# S7CAS-PLEIADES-CARTE-MERE_P06_FPGA2.net
KiCad netlist of a schematic drawn in Altium Designer
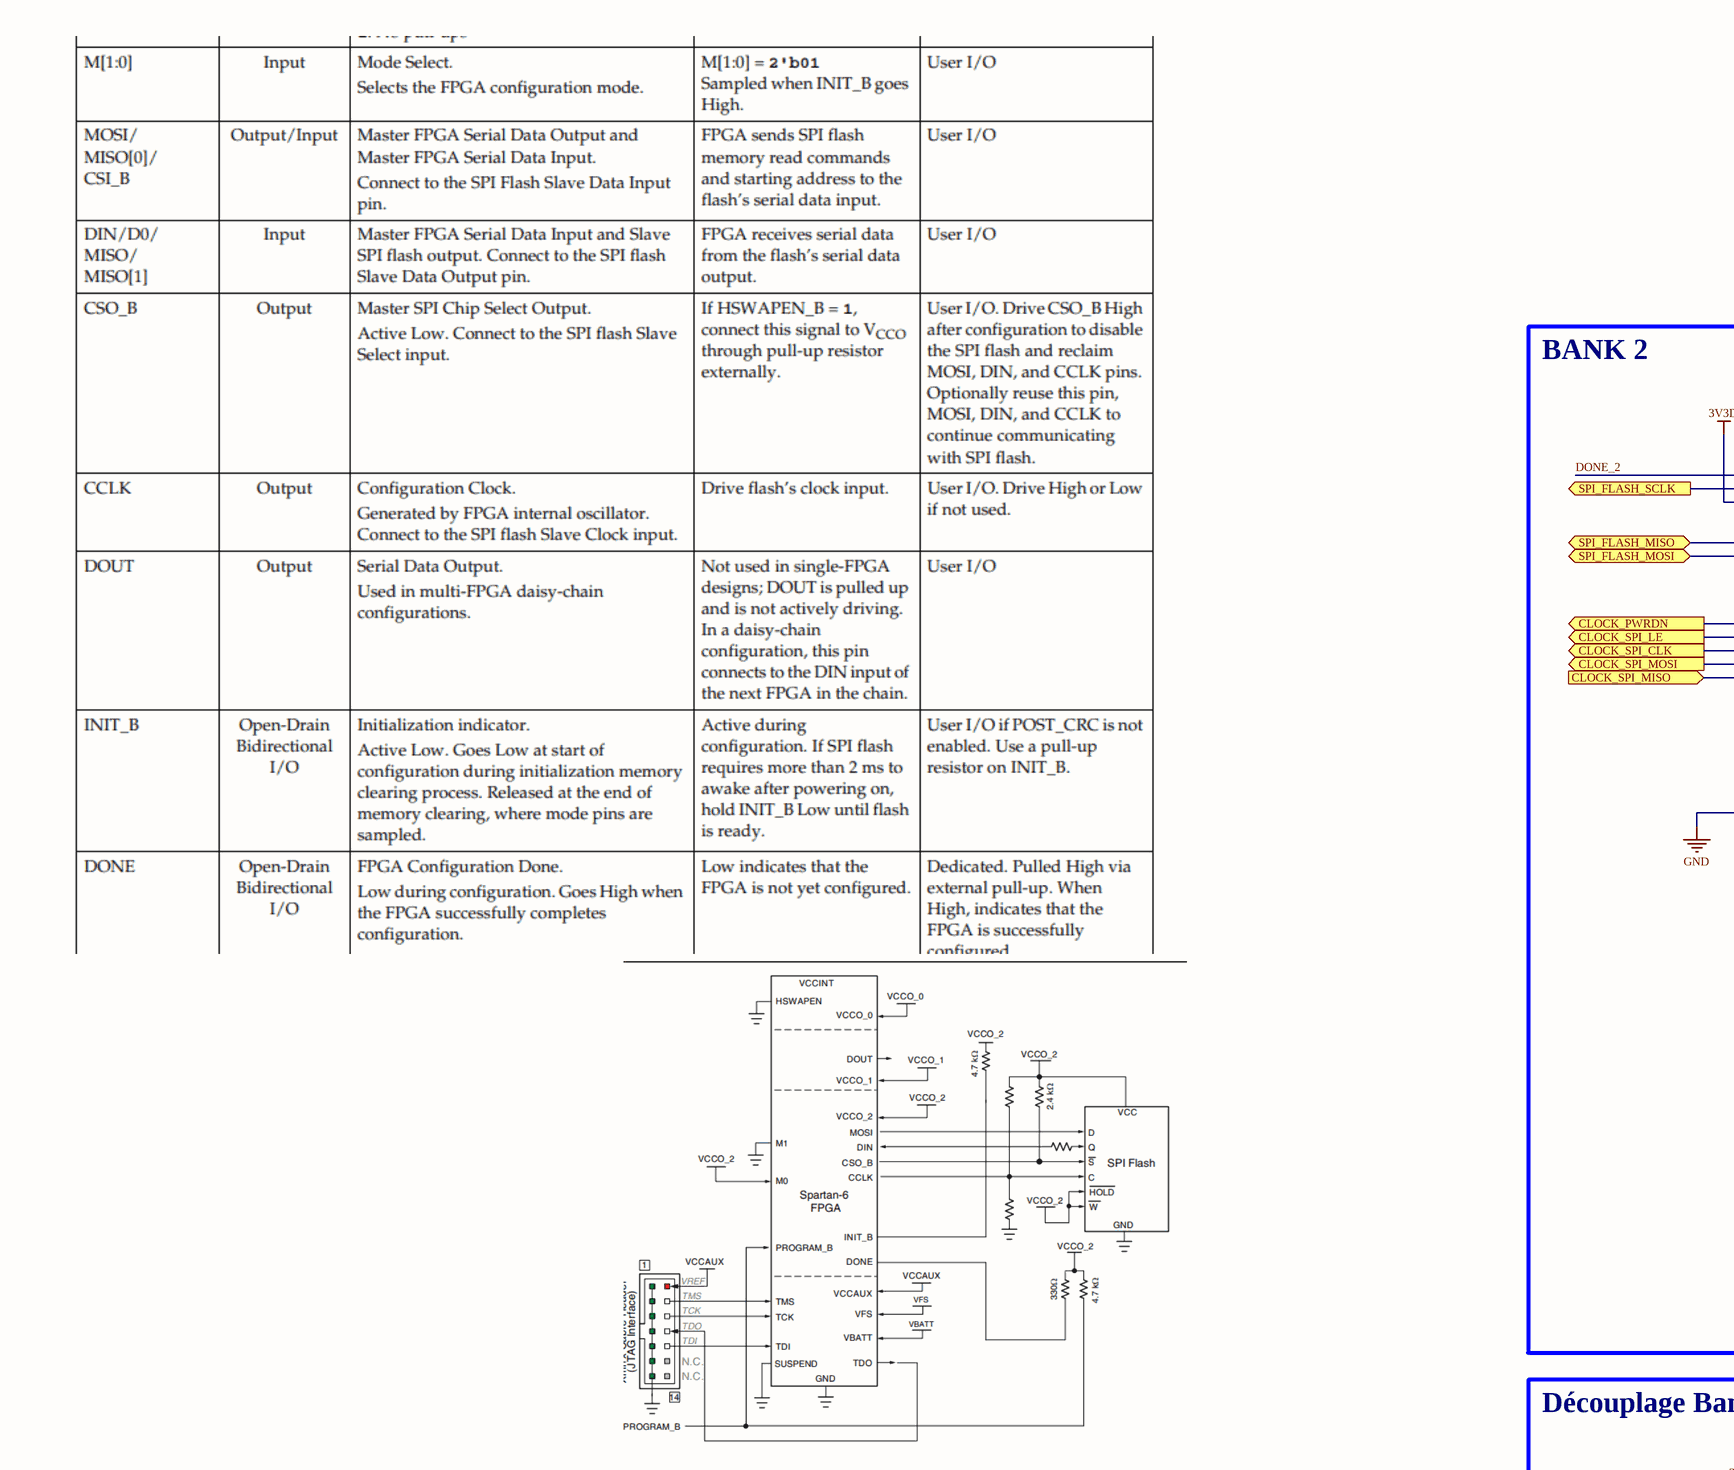
[diagram p0: S7CAS-PLEIADES-CARTE-MERE_P06_FPGA2.SCHDOC, top left]
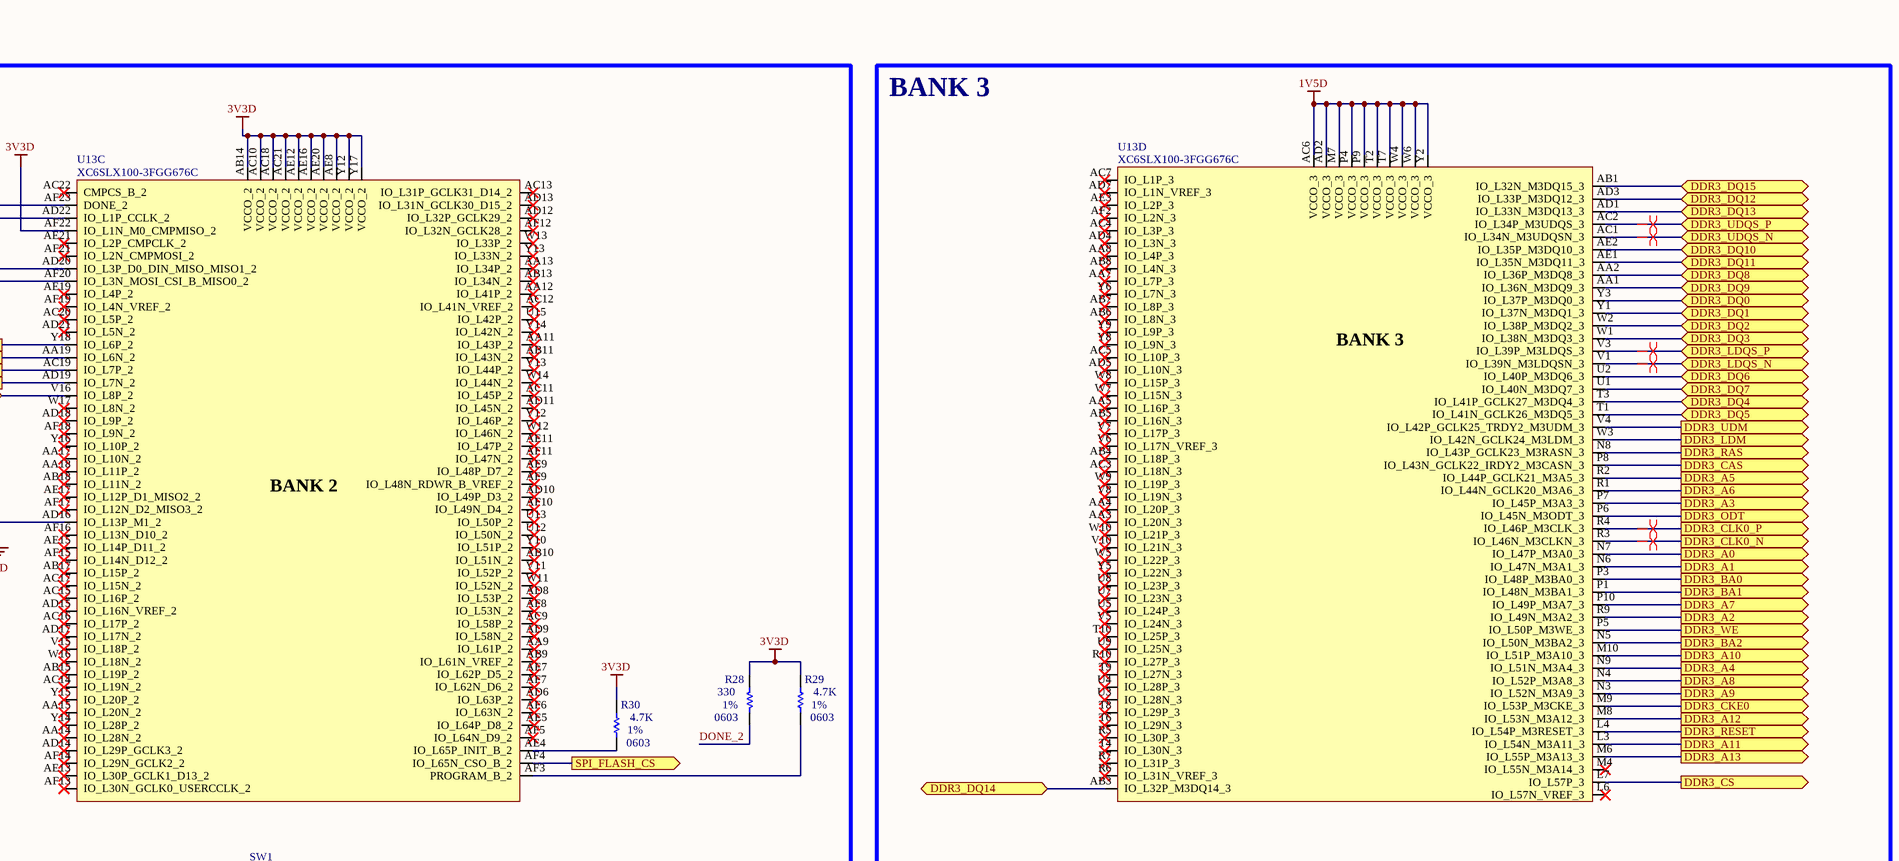
[diagram p1: S7CAS-PLEIADES-CARTE-MERE_P06_FPGA2.SCHDOC, top right]
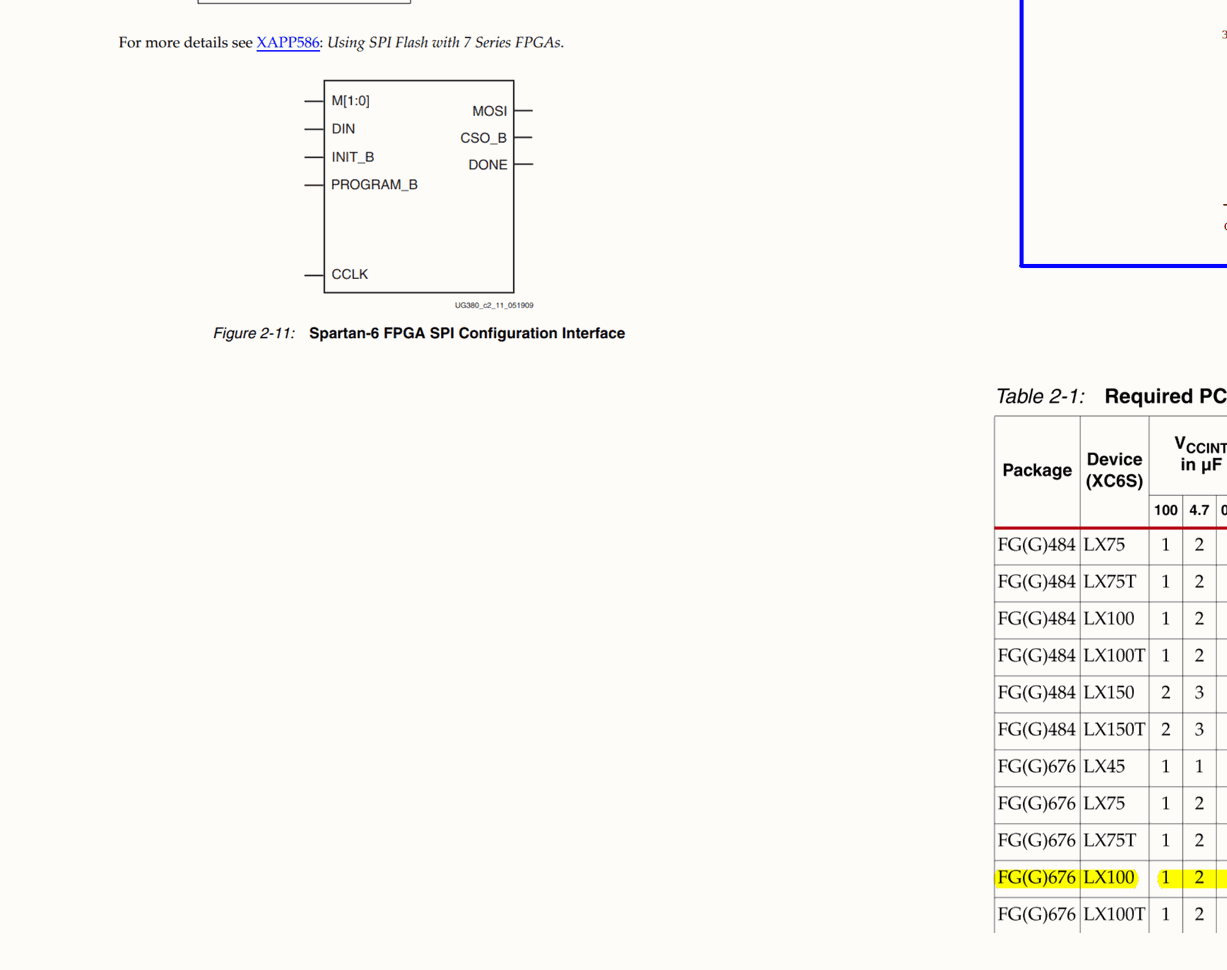
[diagram p2: S7CAS-PLEIADES-CARTE-MERE_P06_FPGA2.SCHDOC, bottom left]
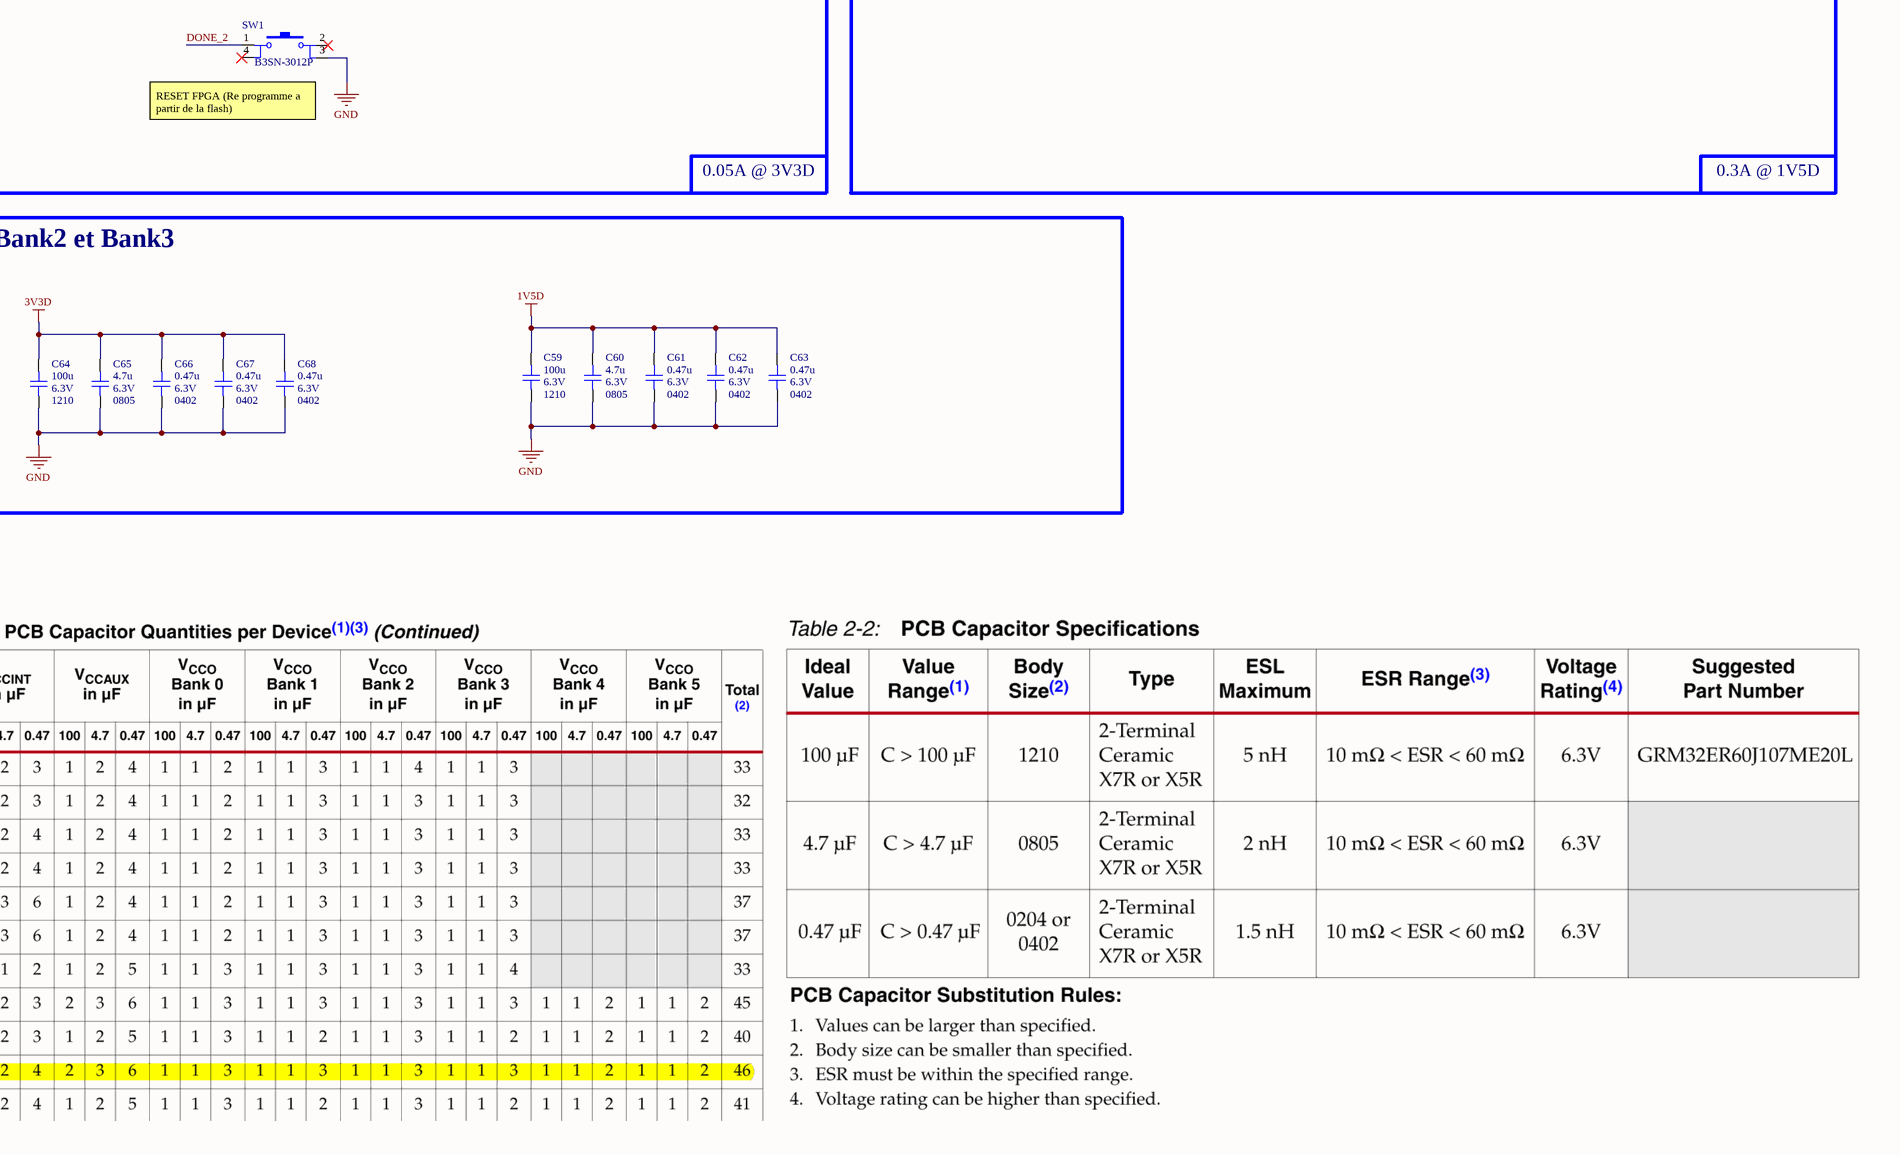
[diagram p3: S7CAS-PLEIADES-CARTE-MERE_P06_FPGA2.SCHDOC, bottom right]

(export (version "E")
  (design (tool "Eeschema 10.0.6"))
  (components
    (comp (ref "C59")
      (value "100u")
      (footprint "CAP_1210")
      (description "CAP - 1210")
      (fields
        (field (name "VOLTAGE") "6.3V")
        (field (name "PACKAGE") "1210")
        (field (name "CREATEDBY") "Jonathan Bouchard")
      )
      (libsource (lib "s7cas_lib2023") (part "CAP - 1210"))
    )
    (comp (ref "C60")
      (value "4.7u")
      (footprint "CAP_0805")
      (description "CAP - 0805")
      (fields
        (field (name "VOLTAGE") "6.3V")
        (field (name "PACKAGE") "0805")
        (field (name "CREATEDBY") "Jonathan Bouchard")
      )
      (libsource (lib "s7cas_lib2023") (part "CAP - 0805"))
    )
    (comp (ref "C61")
      (value "0.47u")
      (footprint "CAP_0402")
      (description "CAP - 0402")
      (fields
        (field (name "VOLTAGE") "6.3V")
        (field (name "PACKAGE") "0402")
        (field (name "CREATEDBY") "Jonathan Bouchard")
      )
      (libsource (lib "s7cas_lib2023") (part "CAP - 0402"))
    )
    (comp (ref "C62")
      (value "0.47u")
      (footprint "CAP_0402")
      (description "CAP - 0402")
      (fields
        (field (name "VOLTAGE") "6.3V")
        (field (name "PACKAGE") "0402")
        (field (name "CREATEDBY") "Jonathan Bouchard")
      )
      (libsource (lib "s7cas_lib2023") (part "CAP - 0402"))
    )
    (comp (ref "C63")
      (value "0.47u")
      (footprint "CAP_0402")
      (description "CAP - 0402")
      (fields
        (field (name "VOLTAGE") "6.3V")
        (field (name "PACKAGE") "0402")
        (field (name "CREATEDBY") "Jonathan Bouchard")
      )
      (libsource (lib "s7cas_lib2023") (part "CAP - 0402"))
    )
    (comp (ref "C64")
      (value "100u")
      (footprint "CAP_1210")
      (description "CAP - 1210")
      (fields
        (field (name "VOLTAGE") "6.3V")
        (field (name "PACKAGE") "1210")
        (field (name "CREATEDBY") "Jonathan Bouchard")
      )
      (libsource (lib "s7cas_lib2023") (part "CAP - 1210"))
    )
    (comp (ref "C65")
      (value "4.7u")
      (footprint "CAP_0805")
      (description "CAP - 0805")
      (fields
        (field (name "VOLTAGE") "6.3V")
        (field (name "PACKAGE") "0805")
        (field (name "CREATEDBY") "Jonathan Bouchard")
      )
      (libsource (lib "s7cas_lib2023") (part "CAP - 0805"))
    )
    (comp (ref "C66")
      (value "0.47u")
      (footprint "CAP_0402")
      (description "CAP - 0402")
      (fields
        (field (name "VOLTAGE") "6.3V")
        (field (name "PACKAGE") "0402")
        (field (name "CREATEDBY") "Jonathan Bouchard")
      )
      (libsource (lib "s7cas_lib2023") (part "CAP - 0402"))
    )
    (comp (ref "C67")
      (value "0.47u")
      (footprint "CAP_0402")
      (description "CAP - 0402")
      (fields
        (field (name "VOLTAGE") "6.3V")
        (field (name "PACKAGE") "0402")
        (field (name "CREATEDBY") "Jonathan Bouchard")
      )
      (libsource (lib "s7cas_lib2023") (part "CAP - 0402"))
    )
    (comp (ref "C68")
      (value "0.47u")
      (footprint "CAP_0402")
      (description "CAP - 0402")
      (fields
        (field (name "VOLTAGE") "6.3V")
        (field (name "PACKAGE") "0402")
        (field (name "CREATEDBY") "Jonathan Bouchard")
      )
      (libsource (lib "s7cas_lib2023") (part "CAP - 0402"))
    )
    (comp (ref "R28")
      (value "330")
      (footprint "RES_0603")
      (description "RES - 0603")
      (fields
        (field (name "PACKAGE") "0603")
        (field (name "PRECISION") "1%")
        (field (name "CREATEDBY") "Jonathan Bouchard")
      )
      (libsource (lib "s7cas_lib2023") (part "RES - 0603"))
    )
    (comp (ref "R29")
      (value "4.7K")
      (footprint "RES_0603")
      (description "RES - 0603")
      (fields
        (field (name "PACKAGE") "0603")
        (field (name "PRECISION") "1%")
        (field (name "CREATEDBY") "Jonathan Bouchard")
      )
      (libsource (lib "s7cas_lib2023") (part "RES - 0603"))
    )
    (comp (ref "R30")
      (value "4.7K")
      (footprint "RES_0603")
      (description "RES - 0603")
      (fields
        (field (name "PACKAGE") "0603")
        (field (name "PRECISION") "1%")
        (field (name "CREATEDBY") "Jonathan Bouchard")
      )
      (libsource (lib "s7cas_lib2023") (part "RES - 0603"))
    )
    (comp (ref "SW1")
      (value "B3SN-3012P")
      (footprint "SWI_TACT_B3SN-3012P")
      (description "SWI - TACT SPST-NO 0.05A 24V - 4-SMD")
      (fields
        (field (name "MFG") "Omron")
        (field (name "VOLTAGE") "24V")
        (field (name "CREATEDBY") "Jonathan Bouchard")
      )
      (libsource (lib "s7cas_lib2023") (part "SWI_TACT_B3SN-3012P"))
    )
    (comp (ref "U13")
      (value "XC6SLX100-3FGG676C")
      (footprint "FPGA_XILINX_FGG676")
      (description "FPGA - XILINX SPARTAN 6 480 I/O - BGA-676")
      (fields
        (field (name "VOLTAGE") "1.14 V ~ 1.26 V")
        (field (name "MFG") "Xilinx")
        (field (name "CREATEDBY") "Jonathan Bouchard")
      )
      (libsource (lib "s7cas_lib2023") (part "FPGA_XC6SLX100-3FGG676C"))
    )
  )
  (nets
    (net (code "1") (name "/CLOCK_PWRDN") (class "Default")
      (node (ref "U13") (pin "Y18") (pinfunction "IO_L6P_2_Y18") (pintype "passive"))
    )
    (net (code "2") (name "/CLOCK_SPI_CLK") (class "Default")
      (node (ref "U13") (pin "AC19") (pinfunction "IO_L7P_2_AC19") (pintype "passive"))
    )
    (net (code "3") (name "/CLOCK_SPI_LE") (class "Default")
      (node (ref "U13") (pin "AA19") (pinfunction "IO_L6N_2_AA19") (pintype "passive"))
    )
    (net (code "4") (name "/CLOCK_SPI_MISO") (class "Default")
      (node (ref "U13") (pin "V16") (pinfunction "IO_L8P_2_V16") (pintype "passive"))
    )
    (net (code "5") (name "/CLOCK_SPI_MOSI") (class "Default")
      (node (ref "U13") (pin "AD19") (pinfunction "IO_L7N_2_AD19") (pintype "passive"))
    )
    (net (code "6") (name "/DDR3_A0") (class "Default")
      (node (ref "U13") (pin "N7") (pinfunction "IO_L47P_M3A0_3_N7") (pintype "passive"))
    )
    (net (code "7") (name "/DDR3_A1") (class "Default")
      (node (ref "U13") (pin "N6") (pinfunction "IO_L47N_M3A1_3_N6") (pintype "passive"))
    )
    (net (code "8") (name "/DDR3_A2") (class "Default")
      (node (ref "U13") (pin "R9") (pinfunction "IO_L49N_M3A2_3_R9") (pintype "passive"))
    )
    (net (code "9") (name "/DDR3_A3") (class "Default")
      (node (ref "U13") (pin "P7") (pinfunction "IO_L45P_M3A3_3_P7") (pintype "passive"))
    )
    (net (code "10") (name "/DDR3_A4") (class "Default")
      (node (ref "U13") (pin "N9") (pinfunction "IO_L51N_M3A4_3_N9") (pintype "passive"))
    )
    (net (code "11") (name "/DDR3_A5") (class "Default")
      (node (ref "U13") (pin "R2") (pinfunction "IO_L44P_GCLK21_M3A5_3_R2") (pintype "passive"))
    )
    (net (code "12") (name "/DDR3_A6") (class "Default")
      (node (ref "U13") (pin "R1") (pinfunction "IO_L44N_GCLK20_M3A6_3_R1") (pintype "passive"))
    )
    (net (code "13") (name "/DDR3_A7") (class "Default")
      (node (ref "U13") (pin "P10") (pinfunction "IO_L49P_M3A7_3_P10") (pintype "passive"))
    )
    (net (code "14") (name "/DDR3_A8") (class "Default")
      (node (ref "U13") (pin "N4") (pinfunction "IO_L52P_M3A8_3_N4") (pintype "passive"))
    )
    (net (code "15") (name "/DDR3_A9") (class "Default")
      (node (ref "U13") (pin "N3") (pinfunction "IO_L52N_M3A9_3_N3") (pintype "passive"))
    )
    (net (code "16") (name "/DDR3_A10") (class "Default")
      (node (ref "U13") (pin "M10") (pinfunction "IO_L51P_M3A10_3_M10") (pintype "passive"))
    )
    (net (code "17") (name "/DDR3_A11") (class "Default")
      (node (ref "U13") (pin "L3") (pinfunction "IO_L54N_M3A11_3_L3") (pintype "passive"))
    )
    (net (code "18") (name "/DDR3_A12") (class "Default")
      (node (ref "U13") (pin "M8") (pinfunction "IO_L53N_M3A12_3_M8") (pintype "passive"))
    )
    (net (code "19") (name "/DDR3_A13") (class "Default")
      (node (ref "U13") (pin "M6") (pinfunction "IO_L55P_M3A13_3_M6") (pintype "passive"))
    )
    (net (code "20") (name "/DDR3_BA0") (class "Default")
      (node (ref "U13") (pin "P3") (pinfunction "IO_L48P_M3BA0_3_P3") (pintype "passive"))
    )
    (net (code "21") (name "/DDR3_BA1") (class "Default")
      (node (ref "U13") (pin "P1") (pinfunction "IO_L48N_M3BA1_3_P1") (pintype "passive"))
    )
    (net (code "22") (name "/DDR3_BA2") (class "Default")
      (node (ref "U13") (pin "N5") (pinfunction "IO_L50N_M3BA2_3_N5") (pintype "passive"))
    )
    (net (code "23") (name "/DDR3_CAS") (class "Default")
      (node (ref "U13") (pin "P8") (pinfunction "IO_L43N_GCLK22_IRDY2_M3CASN_3_P8") (pintype "passive"))
    )
    (net (code "24") (name "/DDR3_CKE0") (class "Default")
      (node (ref "U13") (pin "M9") (pinfunction "IO_L53P_M3CKE_3_M9") (pintype "passive"))
    )
    (net (code "25") (name "/DDR3_CLK0_N") (class "Default")
      (node (ref "U13") (pin "R3") (pinfunction "IO_L46N_M3CLKN_3_R3") (pintype "passive"))
    )
    (net (code "26") (name "/DDR3_CLK0_P") (class "Default")
      (node (ref "U13") (pin "R4") (pinfunction "IO_L46P_M3CLK_3_R4") (pintype "passive"))
    )
    (net (code "27") (name "/DDR3_CS") (class "Default")
      (node (ref "U13") (pin "L7") (pinfunction "IO_L57P_3_L7") (pintype "passive"))
    )
    (net (code "28") (name "/DDR3_DQ0") (class "Default")
      (node (ref "U13") (pin "Y3") (pinfunction "IO_L37P_M3DQ0_3_Y3") (pintype "passive"))
    )
    (net (code "29") (name "/DDR3_DQ1") (class "Default")
      (node (ref "U13") (pin "Y1") (pinfunction "IO_L37N_M3DQ1_3_Y1") (pintype "passive"))
    )
    (net (code "30") (name "/DDR3_DQ2") (class "Default")
      (node (ref "U13") (pin "W2") (pinfunction "IO_L38P_M3DQ2_3_W2") (pintype "passive"))
    )
    (net (code "31") (name "/DDR3_DQ3") (class "Default")
      (node (ref "U13") (pin "W1") (pinfunction "IO_L38N_M3DQ3_3_W1") (pintype "passive"))
    )
    (net (code "32") (name "/DDR3_DQ4") (class "Default")
      (node (ref "U13") (pin "T3") (pinfunction "IO_L41P_GCLK27_M3DQ4_3_T3") (pintype "passive"))
    )
    (net (code "33") (name "/DDR3_DQ5") (class "Default")
      (node (ref "U13") (pin "T1") (pinfunction "IO_L41N_GCLK26_M3DQ5_3_T1") (pintype "passive"))
    )
    (net (code "34") (name "/DDR3_DQ6") (class "Default")
      (node (ref "U13") (pin "U2") (pinfunction "IO_L40P_M3DQ6_3_U2") (pintype "passive"))
    )
    (net (code "35") (name "/DDR3_DQ7") (class "Default")
      (node (ref "U13") (pin "U1") (pinfunction "IO_L40N_M3DQ7_3_U1") (pintype "passive"))
    )
    (net (code "36") (name "/DDR3_DQ8") (class "Default")
      (node (ref "U13") (pin "AA2") (pinfunction "IO_L36P_M3DQ8_3_AA2") (pintype "passive"))
    )
    (net (code "37") (name "/DDR3_DQ9") (class "Default")
      (node (ref "U13") (pin "AA1") (pinfunction "IO_L36N_M3DQ9_3_AA1") (pintype "passive"))
    )
    (net (code "38") (name "/DDR3_DQ10") (class "Default")
      (node (ref "U13") (pin "AE2") (pinfunction "IO_L35P_M3DQ10_3_AE2") (pintype "passive"))
    )
    (net (code "39") (name "/DDR3_DQ11") (class "Default")
      (node (ref "U13") (pin "AE1") (pinfunction "IO_L35N_M3DQ11_3_AE1") (pintype "passive"))
    )
    (net (code "40") (name "/DDR3_DQ12") (class "Default")
      (node (ref "U13") (pin "AD3") (pinfunction "IO_L33P_M3DQ12_3_AD3") (pintype "passive"))
    )
    (net (code "41") (name "/DDR3_DQ13") (class "Default")
      (node (ref "U13") (pin "AD1") (pinfunction "IO_L33N_M3DQ13_3_AD1") (pintype "passive"))
    )
    (net (code "42") (name "/DDR3_DQ14") (class "Default")
      (node (ref "U13") (pin "AB3") (pinfunction "IO_L32P_M3DQ14_3_AB3") (pintype "passive"))
    )
    (net (code "43") (name "/DDR3_DQ15") (class "Default")
      (node (ref "U13") (pin "AB1") (pinfunction "IO_L32N_M3DQ15_3_AB1") (pintype "passive"))
    )
    (net (code "44") (name "/DDR3_LDM") (class "Default")
      (node (ref "U13") (pin "W3") (pinfunction "IO_L42N_GCLK24_M3LDM_3_W3") (pintype "passive"))
    )
    (net (code "45") (name "/DDR3_LDQS_N") (class "Default")
      (node (ref "U13") (pin "V1") (pinfunction "IO_L39N_M3LDQSN_3_V1") (pintype "passive"))
    )
    (net (code "46") (name "/DDR3_LDQS_P") (class "Default")
      (node (ref "U13") (pin "V3") (pinfunction "IO_L39P_M3LDQS_3_V3") (pintype "passive"))
    )
    (net (code "47") (name "/DDR3_ODT") (class "Default")
      (node (ref "U13") (pin "P6") (pinfunction "IO_L45N_M3ODT_3_P6") (pintype "passive"))
    )
    (net (code "48") (name "/DDR3_RAS") (class "Default")
      (node (ref "U13") (pin "N8") (pinfunction "IO_L43P_GCLK23_M3RASN_3_N8") (pintype "passive"))
    )
    (net (code "49") (name "/DDR3_RESET") (class "Default")
      (node (ref "U13") (pin "L4") (pinfunction "IO_L54P_M3RESET_3_L4") (pintype "passive"))
    )
    (net (code "50") (name "/DDR3_UDM") (class "Default")
      (node (ref "U13") (pin "V4") (pinfunction "IO_L42P_GCLK25_TRDY2_M3UDM_3_V4") (pintype "passive"))
    )
    (net (code "51") (name "/DDR3_UDQS_N") (class "Default")
      (node (ref "U13") (pin "AC1") (pinfunction "IO_L34N_M3UDQSN_3_AC1") (pintype "passive"))
    )
    (net (code "52") (name "/DDR3_UDQS_P") (class "Default")
      (node (ref "U13") (pin "AC2") (pinfunction "IO_L34P_M3UDQS_3_AC2") (pintype "passive"))
    )
    (net (code "53") (name "/DDR3_WE") (class "Default")
      (node (ref "U13") (pin "P5") (pinfunction "IO_L50P_M3WE_3_P5") (pintype "passive"))
    )
    (net (code "54") (name "/DONE_2") (class "Default")
      (node (ref "R28") (pin "1") (pinfunction "1_1") (pintype "passive"))
      (node (ref "SW1") (pin "1") (pinfunction "1_1") (pintype "passive"))
      (node (ref "U13") (pin "AF23") (pinfunction "DONE_2_AF23") (pintype "passive"))
    )
    (net (code "55") (name "/SPI_FLASH_CS") (class "Default")
      (node (ref "U13") (pin "AF4") (pinfunction "IO_L65N_CSO_B_2_AF4") (pintype "passive"))
    )
    (net (code "56") (name "/SPI_FLASH_MISO") (class "Default")
      (node (ref "U13") (pin "AD20") (pinfunction "IO_L3P_D0_DIN_MISO_MISO1_2_AD20") (pintype "passive"))
    )
    (net (code "57") (name "/SPI_FLASH_MOSI") (class "Default")
      (node (ref "U13") (pin "AF20") (pinfunction "IO_L3N_MOSI_CSI_B_MISO0_2_AF20") (pintype "passive"))
    )
    (net (code "58") (name "/SPI_FLASH_SCLK") (class "Default")
      (node (ref "U13") (pin "AD22") (pinfunction "IO_L1P_CCLK_2_AD22") (pintype "passive"))
    )
    (net (code "59") (name "1V5D") (class "Default")
      (node (ref "C59") (pin "2") (pinfunction "2_2") (pintype "passive"))
      (node (ref "C60") (pin "2") (pinfunction "2_2") (pintype "passive"))
      (node (ref "C61") (pin "2") (pinfunction "2_2") (pintype "passive"))
      (node (ref "C62") (pin "2") (pinfunction "2_2") (pintype "passive"))
      (node (ref "C63") (pin "2") (pinfunction "2_2") (pintype "passive"))
      (node (ref "U13") (pin "AC6") (pinfunction "VCCO_3_AC6") (pintype "passive"))
      (node (ref "U13") (pin "AD2") (pinfunction "VCCO_3_AD2") (pintype "passive"))
      (node (ref "U13") (pin "M7") (pinfunction "VCCO_3_M7") (pintype "passive"))
      (node (ref "U13") (pin "P4") (pinfunction "VCCO_3_P4") (pintype "passive"))
      (node (ref "U13") (pin "P9") (pinfunction "VCCO_3_P9") (pintype "passive"))
      (node (ref "U13") (pin "T2") (pinfunction "VCCO_3_T2") (pintype "passive"))
      (node (ref "U13") (pin "T7") (pinfunction "VCCO_3_T7") (pintype "passive"))
      (node (ref "U13") (pin "W4") (pinfunction "VCCO_3_W4") (pintype "passive"))
      (node (ref "U13") (pin "W6") (pinfunction "VCCO_3_W6") (pintype "passive"))
      (node (ref "U13") (pin "Y2") (pinfunction "VCCO_3_Y2") (pintype "passive"))
    )
    (net (code "60") (name "3V3D") (class "Default")
      (node (ref "C64") (pin "2") (pinfunction "2_2") (pintype "passive"))
      (node (ref "C65") (pin "2") (pinfunction "2_2") (pintype "passive"))
      (node (ref "C66") (pin "2") (pinfunction "2_2") (pintype "passive"))
      (node (ref "C67") (pin "2") (pinfunction "2_2") (pintype "passive"))
      (node (ref "C68") (pin "2") (pinfunction "2_2") (pintype "passive"))
      (node (ref "R28") (pin "2") (pinfunction "2_2") (pintype "passive"))
      (node (ref "R29") (pin "2") (pinfunction "2_2") (pintype "passive"))
      (node (ref "R30") (pin "2") (pinfunction "2_2") (pintype "passive"))
      (node (ref "U13") (pin "AB14") (pinfunction "VCCO_2_AB14") (pintype "passive"))
      (node (ref "U13") (pin "AC10") (pinfunction "VCCO_2_AC10") (pintype "passive"))
      (node (ref "U13") (pin "AC18") (pinfunction "VCCO_2_AC18") (pintype "passive"))
      (node (ref "U13") (pin "AC21") (pinfunction "VCCO_2_AC21") (pintype "passive"))
      (node (ref "U13") (pin "AE12") (pinfunction "VCCO_2_AE12") (pintype "passive"))
      (node (ref "U13") (pin "AE16") (pinfunction "VCCO_2_AE16") (pintype "passive"))
      (node (ref "U13") (pin "AE20") (pinfunction "VCCO_2_AE20") (pintype "passive"))
      (node (ref "U13") (pin "AE8") (pinfunction "VCCO_2_AE8") (pintype "passive"))
      (node (ref "U13") (pin "AF22") (pinfunction "IO_L1N_M0_CMPMISO_2_AF22") (pintype "passive"))
      (node (ref "U13") (pin "Y12") (pinfunction "VCCO_2_Y12") (pintype "passive"))
      (node (ref "U13") (pin "Y17") (pinfunction "VCCO_2_Y17") (pintype "passive"))
    )
    (net (code "61") (name "GND") (class "Default")
      (node (ref "C59") (pin "1") (pinfunction "1_1") (pintype "passive"))
      (node (ref "C60") (pin "1") (pinfunction "1_1") (pintype "passive"))
      (node (ref "C61") (pin "1") (pinfunction "1_1") (pintype "passive"))
      (node (ref "C62") (pin "1") (pinfunction "1_1") (pintype "passive"))
      (node (ref "C63") (pin "1") (pinfunction "1_1") (pintype "passive"))
      (node (ref "C64") (pin "1") (pinfunction "1_1") (pintype "passive"))
      (node (ref "C65") (pin "1") (pinfunction "1_1") (pintype "passive"))
      (node (ref "C66") (pin "1") (pinfunction "1_1") (pintype "passive"))
      (node (ref "C67") (pin "1") (pinfunction "1_1") (pintype "passive"))
      (node (ref "C68") (pin "1") (pinfunction "1_1") (pintype "passive"))
      (node (ref "SW1") (pin "3") (pinfunction "3_3") (pintype "passive"))
      (node (ref "U13") (pin "AD16") (pinfunction "IO_L13P_M1_2_AD16") (pintype "passive"))
    )
    (net (code "62") (name "Net-(U13C-IO_L65P_INIT_B_2)") (class "Default")
      (node (ref "R30") (pin "1") (pinfunction "1_1") (pintype "passive"))
      (node (ref "U13") (pin "AE4") (pinfunction "IO_L65P_INIT_B_2_AE4") (pintype "passive"))
    )
    (net (code "63") (name "Net-(U13C-PROGRAM_B_2)") (class "Default")
      (node (ref "R29") (pin "1") (pinfunction "1_1") (pintype "passive"))
      (node (ref "U13") (pin "AF3") (pinfunction "PROGRAM_B_2_AF3") (pintype "passive"))
    )
    (net (code "64") (name "unconnected-(SW1-Pad2)") (class "Default")
      (node (ref "SW1") (pin "2") (pinfunction "2_2") (pintype "passive+no_connect"))
    )
    (net (code "65") (name "unconnected-(SW1-Pad4)") (class "Default")
      (node (ref "SW1") (pin "4") (pinfunction "4_4") (pintype "passive+no_connect"))
    )
    (net (code "66") (name "unconnected-(U13C-CMPCS_B_2-PadAC22)") (class "Default")
      (node (ref "U13") (pin "AC22") (pinfunction "CMPCS_B_2_AC22") (pintype "passive+no_connect"))
    )
    (net (code "67") (name "unconnected-(U13C-IO_L2N_CMPMOSI_2-PadAF21)") (class "Default")
      (node (ref "U13") (pin "AF21") (pinfunction "IO_L2N_CMPMOSI_2_AF21") (pintype "passive+no_connect"))
    )
    (net (code "68") (name "unconnected-(U13C-IO_L2P_CMPCLK_2-PadAE21)") (class "Default")
      (node (ref "U13") (pin "AE21") (pinfunction "IO_L2P_CMPCLK_2_AE21") (pintype "passive+no_connect"))
    )
    (net (code "69") (name "unconnected-(U13C-IO_L4N_VREF_2-PadAF19)") (class "Default")
      (node (ref "U13") (pin "AF19") (pinfunction "IO_L4N_VREF_2_AF19") (pintype "passive+no_connect"))
    )
    (net (code "70") (name "unconnected-(U13C-IO_L4P_2-PadAE19)") (class "Default")
      (node (ref "U13") (pin "AE19") (pinfunction "IO_L4P_2_AE19") (pintype "passive+no_connect"))
    )
    (net (code "71") (name "unconnected-(U13C-IO_L5N_2-PadAD21)") (class "Default")
      (node (ref "U13") (pin "AD21") (pinfunction "IO_L5N_2_AD21") (pintype "passive+no_connect"))
    )
    (net (code "72") (name "unconnected-(U13C-IO_L5P_2-PadAC20)") (class "Default")
      (node (ref "U13") (pin "AC20") (pinfunction "IO_L5P_2_AC20") (pintype "passive+no_connect"))
    )
    (net (code "73") (name "unconnected-(U13C-IO_L8N_2-PadW17)") (class "Default")
      (node (ref "U13") (pin "W17") (pinfunction "IO_L8N_2_W17") (pintype "passive+no_connect"))
    )
    (net (code "74") (name "unconnected-(U13C-IO_L9N_2-PadAF18)") (class "Default")
      (node (ref "U13") (pin "AF18") (pinfunction "IO_L9N_2_AF18") (pintype "passive+no_connect"))
    )
    (net (code "75") (name "unconnected-(U13C-IO_L9P_2-PadAD18)") (class "Default")
      (node (ref "U13") (pin "AD18") (pinfunction "IO_L9P_2_AD18") (pintype "passive+no_connect"))
    )
    (net (code "76") (name "unconnected-(U13C-IO_L10N_2-PadAA17)") (class "Default")
      (node (ref "U13") (pin "AA17") (pinfunction "IO_L10N_2_AA17") (pintype "passive+no_connect"))
    )
    (net (code "77") (name "unconnected-(U13C-IO_L10P_2-PadY16)") (class "Default")
      (node (ref "U13") (pin "Y16") (pinfunction "IO_L10P_2_Y16") (pintype "passive+no_connect"))
    )
    (net (code "78") (name "unconnected-(U13C-IO_L11N_2-PadAB18)") (class "Default")
      (node (ref "U13") (pin "AB18") (pinfunction "IO_L11N_2_AB18") (pintype "passive+no_connect"))
    )
    (net (code "79") (name "unconnected-(U13C-IO_L11P_2-PadAA18)") (class "Default")
      (node (ref "U13") (pin "AA18") (pinfunction "IO_L11P_2_AA18") (pintype "passive+no_connect"))
    )
    (net (code "80") (name "unconnected-(U13C-IO_L12N_D2_MISO3_2-PadAF17)") (class "Default")
      (node (ref "U13") (pin "AF17") (pinfunction "IO_L12N_D2_MISO3_2_AF17") (pintype "passive+no_connect"))
    )
    (net (code "81") (name "unconnected-(U13C-IO_L12P_D1_MISO2_2-PadAE17)") (class "Default")
      (node (ref "U13") (pin "AE17") (pinfunction "IO_L12P_D1_MISO2_2_AE17") (pintype "passive+no_connect"))
    )
    (net (code "82") (name "unconnected-(U13C-IO_L13N_D10_2-PadAF16)") (class "Default")
      (node (ref "U13") (pin "AF16") (pinfunction "IO_L13N_D10_2_AF16") (pintype "passive+no_connect"))
    )
    (net (code "83") (name "unconnected-(U13C-IO_L14N_D12_2-PadAF15)") (class "Default")
      (node (ref "U13") (pin "AF15") (pinfunction "IO_L14N_D12_2_AF15") (pintype "passive+no_connect"))
    )
    (net (code "84") (name "unconnected-(U13C-IO_L14P_D11_2-PadAE15)") (class "Default")
      (node (ref "U13") (pin "AE15") (pinfunction "IO_L14P_D11_2_AE15") (pintype "passive+no_connect"))
    )
    (net (code "85") (name "unconnected-(U13C-IO_L15N_2-PadAC17)") (class "Default")
      (node (ref "U13") (pin "AC17") (pinfunction "IO_L15N_2_AC17") (pintype "passive+no_connect"))
    )
    (net (code "86") (name "unconnected-(U13C-IO_L15P_2-PadAB17)") (class "Default")
      (node (ref "U13") (pin "AB17") (pinfunction "IO_L15P_2_AB17") (pintype "passive+no_connect"))
    )
    (net (code "87") (name "unconnected-(U13C-IO_L16N_VREF_2-PadAD15)") (class "Default")
      (node (ref "U13") (pin "AD15") (pinfunction "IO_L16N_VREF_2_AD15") (pintype "passive+no_connect"))
    )
    (net (code "88") (name "unconnected-(U13C-IO_L16P_2-PadAC15)") (class "Default")
      (node (ref "U13") (pin "AC15") (pinfunction "IO_L16P_2_AC15") (pintype "passive+no_connect"))
    )
    (net (code "89") (name "unconnected-(U13C-IO_L17N_2-PadAD17)") (class "Default")
      (node (ref "U13") (pin "AD17") (pinfunction "IO_L17N_2_AD17") (pintype "passive+no_connect"))
    )
    (net (code "90") (name "unconnected-(U13C-IO_L17P_2-PadAC16)") (class "Default")
      (node (ref "U13") (pin "AC16") (pinfunction "IO_L17P_2_AC16") (pintype "passive+no_connect"))
    )
    (net (code "91") (name "unconnected-(U13C-IO_L18N_2-PadW16)") (class "Default")
      (node (ref "U13") (pin "W16") (pinfunction "IO_L18N_2_W16") (pintype "passive+no_connect"))
    )
    (net (code "92") (name "unconnected-(U13C-IO_L18P_2-PadV15)") (class "Default")
      (node (ref "U13") (pin "V15") (pinfunction "IO_L18P_2_V15") (pintype "passive+no_connect"))
    )
    (net (code "93") (name "unconnected-(U13C-IO_L19N_2-PadAC14)") (class "Default")
      (node (ref "U13") (pin "AC14") (pinfunction "IO_L19N_2_AC14") (pintype "passive+no_connect"))
    )
    (net (code "94") (name "unconnected-(U13C-IO_L19P_2-PadAB15)") (class "Default")
      (node (ref "U13") (pin "AB15") (pinfunction "IO_L19P_2_AB15") (pintype "passive+no_connect"))
    )
    (net (code "95") (name "unconnected-(U13C-IO_L20N_2-PadAA15)") (class "Default")
      (node (ref "U13") (pin "AA15") (pinfunction "IO_L20N_2_AA15") (pintype "passive+no_connect"))
    )
    (net (code "96") (name "unconnected-(U13C-IO_L20P_2-PadY15)") (class "Default")
      (node (ref "U13") (pin "Y15") (pinfunction "IO_L20P_2_Y15") (pintype "passive+no_connect"))
    )
    (net (code "97") (name "unconnected-(U13C-IO_L28N_2-PadAA14)") (class "Default")
      (node (ref "U13") (pin "AA14") (pinfunction "IO_L28N_2_AA14") (pintype "passive+no_connect"))
    )
    (net (code "98") (name "unconnected-(U13C-IO_L28P_2-PadY14)") (class "Default")
      (node (ref "U13") (pin "Y14") (pinfunction "IO_L28P_2_Y14") (pintype "passive+no_connect"))
    )
    (net (code "99") (name "unconnected-(U13C-IO_L29N_GCLK2_2-PadAF14)") (class "Default")
      (node (ref "U13") (pin "AF14") (pinfunction "IO_L29N_GCLK2_2_AF14") (pintype "passive+no_connect"))
    )
    (net (code "100") (name "unconnected-(U13C-IO_L29P_GCLK3_2-PadAD14)") (class "Default")
      (node (ref "U13") (pin "AD14") (pinfunction "IO_L29P_GCLK3_2_AD14") (pintype "passive+no_connect"))
    )
    (net (code "101") (name "unconnected-(U13C-IO_L30N_GCLK0_USERCCLK_2-PadAF13)") (class "Default")
      (node (ref "U13") (pin "AF13") (pinfunction "IO_L30N_GCLK0_USERCCLK_2_AF13") (pintype "passive+no_connect"))
    )
    (net (code "102") (name "unconnected-(U13C-IO_L30P_GCLK1_D13_2-PadAE13)") (class "Default")
      (node (ref "U13") (pin "AE13") (pinfunction "IO_L30P_GCLK1_D13_2_AE13") (pintype "passive+no_connect"))
    )
    (net (code "103") (name "unconnected-(U13C-IO_L31N_GCLK30_D15_2-PadAD13)") (class "Default")
      (node (ref "U13") (pin "AD13") (pinfunction "IO_L31N_GCLK30_D15_2_AD13") (pintype "passive+no_connect"))
    )
    (net (code "104") (name "unconnected-(U13C-IO_L31P_GCLK31_D14_2-PadAC13)") (class "Default")
      (node (ref "U13") (pin "AC13") (pinfunction "IO_L31P_GCLK31_D14_2_AC13") (pintype "passive+no_connect"))
    )
    (net (code "105") (name "unconnected-(U13C-IO_L32N_GCLK28_2-PadAF12)") (class "Default")
      (node (ref "U13") (pin "AF12") (pinfunction "IO_L32N_GCLK28_2_AF12") (pintype "passive+no_connect"))
    )
    (net (code "106") (name "unconnected-(U13C-IO_L32P_GCLK29_2-PadAD12)") (class "Default")
      (node (ref "U13") (pin "AD12") (pinfunction "IO_L32P_GCLK29_2_AD12") (pintype "passive+no_connect"))
    )
    (net (code "107") (name "unconnected-(U13C-IO_L33N_2-PadY13)") (class "Default")
      (node (ref "U13") (pin "Y13") (pinfunction "IO_L33N_2_Y13") (pintype "passive+no_connect"))
    )
    (net (code "108") (name "unconnected-(U13C-IO_L33P_2-PadW13)") (class "Default")
      (node (ref "U13") (pin "W13") (pinfunction "IO_L33P_2_W13") (pintype "passive+no_connect"))
    )
    (net (code "109") (name "unconnected-(U13C-IO_L34N_2-PadAB13)") (class "Default")
      (node (ref "U13") (pin "AB13") (pinfunction "IO_L34N_2_AB13") (pintype "passive+no_connect"))
    )
    (net (code "110") (name "unconnected-(U13C-IO_L34P_2-PadAA13)") (class "Default")
      (node (ref "U13") (pin "AA13") (pinfunction "IO_L34P_2_AA13") (pintype "passive+no_connect"))
    )
    (net (code "111") (name "unconnected-(U13C-IO_L41N_VREF_2-PadAC12)") (class "Default")
      (node (ref "U13") (pin "AC12") (pinfunction "IO_L41N_VREF_2_AC12") (pintype "passive+no_connect"))
    )
    (net (code "112") (name "unconnected-(U13C-IO_L41P_2-PadAA12)") (class "Default")
      (node (ref "U13") (pin "AA12") (pinfunction "IO_L41P_2_AA12") (pintype "passive+no_connect"))
    )
    (net (code "113") (name "unconnected-(U13C-IO_L42N_2-PadV14)") (class "Default")
      (node (ref "U13") (pin "V14") (pinfunction "IO_L42N_2_V14") (pintype "passive+no_connect"))
    )
    (net (code "114") (name "unconnected-(U13C-IO_L42P_2-PadU15)") (class "Default")
      (node (ref "U13") (pin "U15") (pinfunction "IO_L42P_2_U15") (pintype "passive+no_connect"))
    )
    (net (code "115") (name "unconnected-(U13C-IO_L43N_2-PadAB11)") (class "Default")
      (node (ref "U13") (pin "AB11") (pinfunction "IO_L43N_2_AB11") (pintype "passive+no_connect"))
    )
    (net (code "116") (name "unconnected-(U13C-IO_L43P_2-PadAA11)") (class "Default")
      (node (ref "U13") (pin "AA11") (pinfunction "IO_L43P_2_AA11") (pintype "passive+no_connect"))
    )
    (net (code "117") (name "unconnected-(U13C-IO_L44N_2-PadW14)") (class "Default")
      (node (ref "U13") (pin "W14") (pinfunction "IO_L44N_2_W14") (pintype "passive+no_connect"))
    )
    (net (code "118") (name "unconnected-(U13C-IO_L44P_2-PadV13)") (class "Default")
      (node (ref "U13") (pin "V13") (pinfunction "IO_L44P_2_V13") (pintype "passive+no_connect"))
    )
    (net (code "119") (name "unconnected-(U13C-IO_L45N_2-PadAD11)") (class "Default")
      (node (ref "U13") (pin "AD11") (pinfunction "IO_L45N_2_AD11") (pintype "passive+no_connect"))
    )
    (net (code "120") (name "unconnected-(U13C-IO_L45P_2-PadAC11)") (class "Default")
      (node (ref "U13") (pin "AC11") (pinfunction "IO_L45P_2_AC11") (pintype "passive+no_connect"))
    )
    (net (code "121") (name "unconnected-(U13C-IO_L46N_2-PadW12)") (class "Default")
      (node (ref "U13") (pin "W12") (pinfunction "IO_L46N_2_W12") (pintype "passive+no_connect"))
    )
    (net (code "122") (name "unconnected-(U13C-IO_L46P_2-PadV12)") (class "Default")
      (node (ref "U13") (pin "V12") (pinfunction "IO_L46P_2_V12") (pintype "passive+no_connect"))
    )
    (net (code "123") (name "unconnected-(U13C-IO_L47N_2-PadAF11)") (class "Default")
      (node (ref "U13") (pin "AF11") (pinfunction "IO_L47N_2_AF11") (pintype "passive+no_connect"))
    )
    (net (code "124") (name "unconnected-(U13C-IO_L47P_2-PadAE11)") (class "Default")
      (node (ref "U13") (pin "AE11") (pinfunction "IO_L47P_2_AE11") (pintype "passive+no_connect"))
    )
    (net (code "125") (name "unconnected-(U13C-IO_L48N_RDWR_B_VREF_2-PadAF9)") (class "Default")
      (node (ref "U13") (pin "AF9") (pinfunction "IO_L48N_RDWR_B_VREF_2_AF9") (pintype "passive+no_connect"))
    )
    (net (code "126") (name "unconnected-(U13C-IO_L48P_D7_2-PadAE9)") (class "Default")
      (node (ref "U13") (pin "AE9") (pinfunction "IO_L48P_D7_2_AE9") (pintype "passive+no_connect"))
    )
    (net (code "127") (name "unconnected-(U13C-IO_L49N_D4_2-PadAF10)") (class "Default")
      (node (ref "U13") (pin "AF10") (pinfunction "IO_L49N_D4_2_AF10") (pintype "passive+no_connect"))
    )
    (net (code "128") (name "unconnected-(U13C-IO_L49P_D3_2-PadAD10)") (class "Default")
      (node (ref "U13") (pin "AD10") (pinfunction "IO_L49P_D3_2_AD10") (pintype "passive+no_connect"))
    )
    (net (code "129") (name "unconnected-(U13C-IO_L50N_2-PadU12)") (class "Default")
      (node (ref "U13") (pin "U12") (pinfunction "IO_L50N_2_U12") (pintype "passive+no_connect"))
    )
    (net (code "130") (name "unconnected-(U13C-IO_L50P_2-PadU13)") (class "Default")
      (node (ref "U13") (pin "U13") (pinfunction "IO_L50P_2_U13") (pintype "passive+no_connect"))
    )
    (net (code "131") (name "unconnected-(U13C-IO_L51N_2-PadAB10)") (class "Default")
      (node (ref "U13") (pin "AB10") (pinfunction "IO_L51N_2_AB10") (pintype "passive+no_connect"))
    )
    (net (code "132") (name "unconnected-(U13C-IO_L51P_2-PadY10)") (class "Default")
      (node (ref "U13") (pin "Y10") (pinfunction "IO_L51P_2_Y10") (pintype "passive+no_connect"))
    )
    (net (code "133") (name "unconnected-(U13C-IO_L52N_2-PadW11)") (class "Default")
      (node (ref "U13") (pin "W11") (pinfunction "IO_L52N_2_W11") (pintype "passive+no_connect"))
    )
    (net (code "134") (name "unconnected-(U13C-IO_L52P_2-PadV11)") (class "Default")
      (node (ref "U13") (pin "V11") (pinfunction "IO_L52P_2_V11") (pintype "passive+no_connect"))
    )
    (net (code "135") (name "unconnected-(U13C-IO_L53N_2-PadAF8)") (class "Default")
      (node (ref "U13") (pin "AF8") (pinfunction "IO_L53N_2_AF8") (pintype "passive+no_connect"))
    )
    (net (code "136") (name "unconnected-(U13C-IO_L53P_2-PadAD8)") (class "Default")
      (node (ref "U13") (pin "AD8") (pinfunction "IO_L53P_2_AD8") (pintype "passive+no_connect"))
    )
    (net (code "137") (name "unconnected-(U13C-IO_L58N_2-PadAD9)") (class "Default")
      (node (ref "U13") (pin "AD9") (pinfunction "IO_L58N_2_AD9") (pintype "passive+no_connect"))
    )
    (net (code "138") (name "unconnected-(U13C-IO_L58P_2-PadAC9)") (class "Default")
      (node (ref "U13") (pin "AC9") (pinfunction "IO_L58P_2_AC9") (pintype "passive+no_connect"))
    )
    (net (code "139") (name "unconnected-(U13C-IO_L61N_VREF_2-PadAB9)") (class "Default")
      (node (ref "U13") (pin "AB9") (pinfunction "IO_L61N_VREF_2_AB9") (pintype "passive+no_connect"))
    )
    (net (code "140") (name "unconnected-(U13C-IO_L61P_2-PadAA9)") (class "Default")
      (node (ref "U13") (pin "AA9") (pinfunction "IO_L61P_2_AA9") (pintype "passive+no_connect"))
    )
    (net (code "141") (name "unconnected-(U13C-IO_L62N_D6_2-PadAF7)") (class "Default")
      (node (ref "U13") (pin "AF7") (pinfunction "IO_L62N_D6_2_AF7") (pintype "passive+no_connect"))
    )
    (net (code "142") (name "unconnected-(U13C-IO_L62P_D5_2-PadAE7)") (class "Default")
      (node (ref "U13") (pin "AE7") (pinfunction "IO_L62P_D5_2_AE7") (pintype "passive+no_connect"))
    )
    (net (code "143") (name "unconnected-(U13C-IO_L63N_2-PadAF6)") (class "Default")
      (node (ref "U13") (pin "AF6") (pinfunction "IO_L63N_2_AF6") (pintype "passive+no_connect"))
    )
    (net (code "144") (name "unconnected-(U13C-IO_L63P_2-PadAD6)") (class "Default")
      (node (ref "U13") (pin "AD6") (pinfunction "IO_L63P_2_AD6") (pintype "passive+no_connect"))
    )
    (net (code "145") (name "unconnected-(U13C-IO_L64N_D9_2-PadAF5)") (class "Default")
      (node (ref "U13") (pin "AF5") (pinfunction "IO_L64N_D9_2_AF5") (pintype "passive+no_connect"))
    )
    (net (code "146") (name "unconnected-(U13C-IO_L64P_D8_2-PadAE5)") (class "Default")
      (node (ref "U13") (pin "AE5") (pinfunction "IO_L64P_D8_2_AE5") (pintype "passive+no_connect"))
    )
    (net (code "147") (name "unconnected-(U13D-IO_L1N_VREF_3-PadAD7)") (class "Default")
      (node (ref "U13") (pin "AD7") (pinfunction "IO_L1N_VREF_3_AD7") (pintype "passive+no_connect"))
    )
    (net (code "148") (name "unconnected-(U13D-IO_L1P_3-PadAC7)") (class "Default")
      (node (ref "U13") (pin "AC7") (pinfunction "IO_L1P_3_AC7") (pintype "passive+no_connect"))
    )
    (net (code "149") (name "unconnected-(U13D-IO_L2N_3-PadAF2)") (class "Default")
      (node (ref "U13") (pin "AF2") (pinfunction "IO_L2N_3_AF2") (pintype "passive+no_connect"))
    )
    (net (code "150") (name "unconnected-(U13D-IO_L2P_3-PadAE3)") (class "Default")
      (node (ref "U13") (pin "AE3") (pinfunction "IO_L2P_3_AE3") (pintype "passive+no_connect"))
    )
    (net (code "151") (name "unconnected-(U13D-IO_L3N_3-PadAD4)") (class "Default")
      (node (ref "U13") (pin "AD4") (pinfunction "IO_L3N_3_AD4") (pintype "passive+no_connect"))
    )
    (net (code "152") (name "unconnected-(U13D-IO_L3P_3-PadAC4)") (class "Default")
      (node (ref "U13") (pin "AC4") (pinfunction "IO_L3P_3_AC4") (pintype "passive+no_connect"))
    )
    (net (code "153") (name "unconnected-(U13D-IO_L4N_3-PadAB8)") (class "Default")
      (node (ref "U13") (pin "AB8") (pinfunction "IO_L4N_3_AB8") (pintype "passive+no_connect"))
    )
    (net (code "154") (name "unconnected-(U13D-IO_L4P_3-PadAA8)") (class "Default")
      (node (ref "U13") (pin "AA8") (pinfunction "IO_L4P_3_AA8") (pintype "passive+no_connect"))
    )
    (net (code "155") (name "unconnected-(U13D-IO_L7N_3-PadY6)") (class "Default")
      (node (ref "U13") (pin "Y6") (pinfunction "IO_L7N_3_Y6") (pintype "passive+no_connect"))
    )
    (net (code "156") (name "unconnected-(U13D-IO_L7P_3-PadAA7)") (class "Default")
      (node (ref "U13") (pin "AA7") (pinfunction "IO_L7P_3_AA7") (pintype "passive+no_connect"))
    )
    (net (code "157") (name "unconnected-(U13D-IO_L8N_3-PadAB6)") (class "Default")
      (node (ref "U13") (pin "AB6") (pinfunction "IO_L8N_3_AB6") (pintype "passive+no_connect"))
    )
    (net (code "158") (name "unconnected-(U13D-IO_L8P_3-PadAB7)") (class "Default")
      (node (ref "U13") (pin "AB7") (pinfunction "IO_L8P_3_AB7") (pintype "passive+no_connect"))
    )
    (net (code "159") (name "unconnected-(U13D-IO_L9N_3-PadY8)") (class "Default")
      (node (ref "U13") (pin "Y8") (pinfunction "IO_L9N_3_Y8") (pintype "passive+no_connect"))
    )
    (net (code "160") (name "unconnected-(U13D-IO_L9P_3-PadY9)") (class "Default")
      (node (ref "U13") (pin "Y9") (pinfunction "IO_L9P_3_Y9") (pintype "passive+no_connect"))
    )
    (net (code "161") (name "unconnected-(U13D-IO_L10N_3-PadAD5)") (class "Default")
      (node (ref "U13") (pin "AD5") (pinfunction "IO_L10N_3_AD5") (pintype "passive+no_connect"))
    )
    (net (code "162") (name "unconnected-(U13D-IO_L10P_3-PadAC5)") (class "Default")
      (node (ref "U13") (pin "AC5") (pinfunction "IO_L10P_3_AC5") (pintype "passive+no_connect"))
    )
    (net (code "163") (name "unconnected-(U13D-IO_L15N_3-PadW7)") (class "Default")
      (node (ref "U13") (pin "W7") (pinfunction "IO_L15N_3_W7") (pintype "passive+no_connect"))
    )
    (net (code "164") (name "unconnected-(U13D-IO_L15P_3-PadW8)") (class "Default")
      (node (ref "U13") (pin "W8") (pinfunction "IO_L15P_3_W8") (pintype "passive+no_connect"))
    )
    (net (code "165") (name "unconnected-(U13D-IO_L16N_3-PadAB5)") (class "Default")
      (node (ref "U13") (pin "AB5") (pinfunction "IO_L16N_3_AB5") (pintype "passive+no_connect"))
    )
    (net (code "166") (name "unconnected-(U13D-IO_L16P_3-PadAA5)") (class "Default")
      (node (ref "U13") (pin "AA5") (pinfunction "IO_L16P_3_AA5") (pintype "passive+no_connect"))
    )
    (net (code "167") (name "unconnected-(U13D-IO_L17N_VREF_3-PadV6)") (class "Default")
      (node (ref "U13") (pin "V6") (pinfunction "IO_L17N_VREF_3_V6") (pintype "passive+no_connect"))
    )
    (net (code "168") (name "unconnected-(U13D-IO_L17P_3-PadV7)") (class "Default")
      (node (ref "U13") (pin "V7") (pinfunction "IO_L17P_3_V7") (pintype "passive+no_connect"))
    )
    (net (code "169") (name "unconnected-(U13D-IO_L18N_3-PadAC3)") (class "Default")
      (node (ref "U13") (pin "AC3") (pinfunction "IO_L18N_3_AC3") (pintype "passive+no_connect"))
    )
    (net (code "170") (name "unconnected-(U13D-IO_L18P_3-PadAB4)") (class "Default")
      (node (ref "U13") (pin "AB4") (pinfunction "IO_L18P_3_AB4") (pintype "passive+no_connect"))
    )
    (net (code "171") (name "unconnected-(U13D-IO_L19N_3-PadV8)") (class "Default")
      (node (ref "U13") (pin "V8") (pinfunction "IO_L19N_3_V8") (pintype "passive+no_connect"))
    )
    (net (code "172") (name "unconnected-(U13D-IO_L19P_3-PadW9)") (class "Default")
      (node (ref "U13") (pin "W9") (pinfunction "IO_L19P_3_W9") (pintype "passive+no_connect"))
    )
    (net (code "173") (name "unconnected-(U13D-IO_L20N_3-PadAA3)") (class "Default")
      (node (ref "U13") (pin "AA3") (pinfunction "IO_L20N_3_AA3") (pintype "passive+no_connect"))
    )
    (net (code "174") (name "unconnected-(U13D-IO_L20P_3-PadAA4)") (class "Default")
      (node (ref "U13") (pin "AA4") (pinfunction "IO_L20P_3_AA4") (pintype "passive+no_connect"))
    )
    (net (code "175") (name "unconnected-(U13D-IO_L21N_3-PadV10)") (class "Default")
      (node (ref "U13") (pin "V10") (pinfunction "IO_L21N_3_V10") (pintype "passive+no_connect"))
    )
    (net (code "176") (name "unconnected-(U13D-IO_L21P_3-PadW10)") (class "Default")
      (node (ref "U13") (pin "W10") (pinfunction "IO_L21P_3_W10") (pintype "passive+no_connect"))
    )
    (net (code "177") (name "unconnected-(U13D-IO_L22N_3-PadY5)") (class "Default")
      (node (ref "U13") (pin "Y5") (pinfunction "IO_L22N_3_Y5") (pintype "passive+no_connect"))
    )
    (net (code "178") (name "unconnected-(U13D-IO_L22P_3-PadW5)") (class "Default")
      (node (ref "U13") (pin "W5") (pinfunction "IO_L22P_3_W5") (pintype "passive+no_connect"))
    )
    (net (code "179") (name "unconnected-(U13D-IO_L23N_3-PadU7)") (class "Default")
      (node (ref "U13") (pin "U7") (pinfunction "IO_L23N_3_U7") (pintype "passive+no_connect"))
    )
    (net (code "180") (name "unconnected-(U13D-IO_L23P_3-PadU8)") (class "Default")
      (node (ref "U13") (pin "U8") (pinfunction "IO_L23P_3_U8") (pintype "passive+no_connect"))
    )
    (net (code "181") (name "unconnected-(U13D-IO_L24N_3-PadV5)") (class "Default")
      (node (ref "U13") (pin "V5") (pinfunction "IO_L24N_3_V5") (pintype "passive+no_connect"))
    )
    (net (code "182") (name "unconnected-(U13D-IO_L24P_3-PadU5)") (class "Default")
      (node (ref "U13") (pin "U5") (pinfunction "IO_L24P_3_U5") (pintype "passive+no_connect"))
    )
    (net (code "183") (name "unconnected-(U13D-IO_L25N_3-PadU9)") (class "Default")
      (node (ref "U13") (pin "U9") (pinfunction "IO_L25N_3_U9") (pintype "passive+no_connect"))
    )
    (net (code "184") (name "unconnected-(U13D-IO_L25P_3-PadT10)") (class "Default")
      (node (ref "U13") (pin "T10") (pinfunction "IO_L25P_3_T10") (pintype "passive+no_connect"))
    )
    (net (code "185") (name "unconnected-(U13D-IO_L27N_3-PadT9)") (class "Default")
      (node (ref "U13") (pin "T9") (pinfunction "IO_L27N_3_T9") (pintype "passive+no_connect"))
    )
    (net (code "186") (name "unconnected-(U13D-IO_L27P_3-PadR10)") (class "Default")
      (node (ref "U13") (pin "R10") (pinfunction "IO_L27P_3_R10") (pintype "passive+no_connect"))
    )
    (net (code "187") (name "unconnected-(U13D-IO_L28N_3-PadU3)") (class "Default")
      (node (ref "U13") (pin "U3") (pinfunction "IO_L28N_3_U3") (pintype "passive+no_connect"))
    )
    (net (code "188") (name "unconnected-(U13D-IO_L28P_3-PadU4)") (class "Default")
      (node (ref "U13") (pin "U4") (pinfunction "IO_L28P_3_U4") (pintype "passive+no_connect"))
    )
    (net (code "189") (name "unconnected-(U13D-IO_L29N_3-PadT6)") (class "Default")
      (node (ref "U13") (pin "T6") (pinfunction "IO_L29N_3_T6") (pintype "passive+no_connect"))
    )
    (net (code "190") (name "unconnected-(U13D-IO_L29P_3-PadT8)") (class "Default")
      (node (ref "U13") (pin "T8") (pinfunction "IO_L29P_3_T8") (pintype "passive+no_connect"))
    )
    (net (code "191") (name "unconnected-(U13D-IO_L30N_3-PadT4)") (class "Default")
      (node (ref "U13") (pin "T4") (pinfunction "IO_L30N_3_T4") (pintype "passive+no_connect"))
    )
    (net (code "192") (name "unconnected-(U13D-IO_L30P_3-PadR5)") (class "Default")
      (node (ref "U13") (pin "R5") (pinfunction "IO_L30P_3_R5") (pintype "passive+no_connect"))
    )
    (net (code "193") (name "unconnected-(U13D-IO_L31N_VREF_3-PadR6)") (class "Default")
      (node (ref "U13") (pin "R6") (pinfunction "IO_L31N_VREF_3_R6") (pintype "passive+no_connect"))
    )
    (net (code "194") (name "unconnected-(U13D-IO_L31P_3-PadR7)") (class "Default")
      (node (ref "U13") (pin "R7") (pinfunction "IO_L31P_3_R7") (pintype "passive+no_connect"))
    )
    (net (code "195") (name "unconnected-(U13D-IO_L55N_M3A14_3-PadM4)") (class "Default")
      (node (ref "U13") (pin "M4") (pinfunction "IO_L55N_M3A14_3_M4") (pintype "passive+no_connect"))
    )
    (net (code "196") (name "unconnected-(U13D-IO_L57N_VREF_3-PadL6)") (class "Default")
      (node (ref "U13") (pin "L6") (pinfunction "IO_L57N_VREF_3_L6") (pintype "passive+no_connect"))
    )
  )
)
